# Apex_CV_Inputs_UI_v1_0.net
KiCad netlist of a schematic drawn in EAGLE
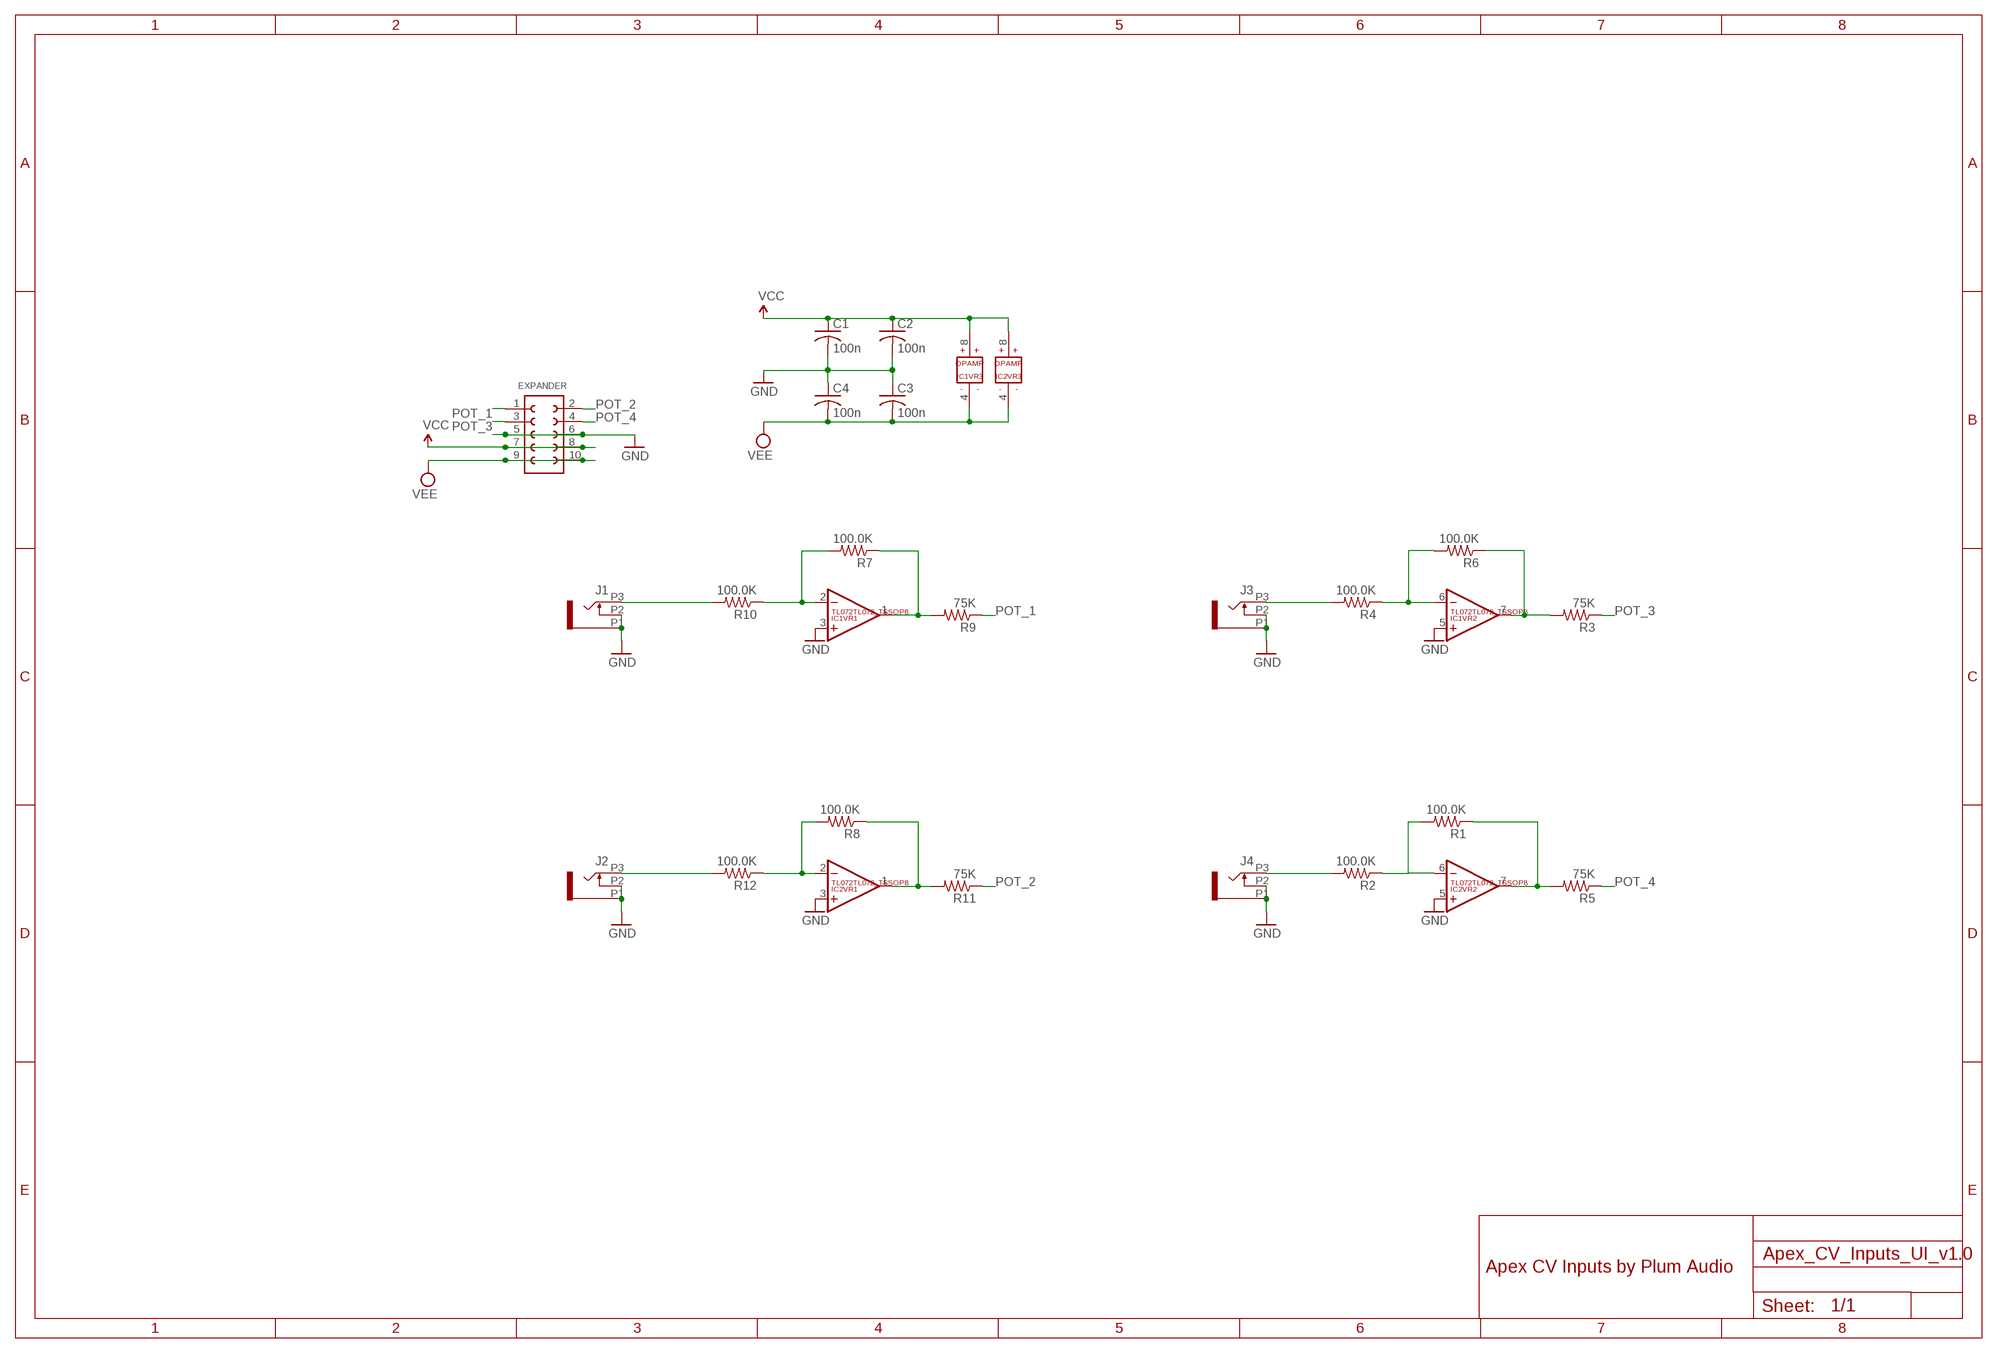
[diagram p0: schematic, sheet 1]

(export (version "E")
  (design (tool "Eeschema 10.0.6"))
  (components
    (comp (ref "C1")
      (value "100n")
      (footprint "eagle-import:C0603")
      (libsource (lib "eagle-import") (part "C-USC0603"))
    )
    (comp (ref "C2")
      (value "100n")
      (footprint "eagle-import:C0603")
      (libsource (lib "eagle-import") (part "C-USC0603"))
    )
    (comp (ref "C3")
      (value "100n")
      (footprint "eagle-import:C0603")
      (libsource (lib "eagle-import") (part "C-USC0603"))
    )
    (comp (ref "C4")
      (value "100n")
      (footprint "eagle-import:C0603")
      (libsource (lib "eagle-import") (part "C-USC0603"))
    )
    (comp (ref "EXPANDER")
      (value "61301021121")
      (footprint "eagle-import:61301021121")
      (libsource (lib "eagle-import") (part "61301021121"))
    )
    (comp (ref "IC1")
      (value "TL072TL072_TSSOP8")
      (footprint "eagle-import:TL072_TSSOP8")
      (libsource (lib "eagle-import") (part "TL072TL072_TSSOP8"))
    )
    (comp (ref "IC2")
      (value "TL072TL072_TSSOP8")
      (footprint "eagle-import:TL072_TSSOP8")
      (libsource (lib "eagle-import") (part "TL072TL072_TSSOP8"))
    )
    (comp (ref "J1")
      (value "OG-PJ301_PJ301_THONKICONN")
      (footprint "eagle-import:OG-PJ301_WQP_PJ_301M6_NO_HOLE")
      (libsource (lib "eagle-import") (part "OG-PJ301_PJ301_THONKICONN"))
    )
    (comp (ref "J2")
      (value "OG-PJ301_PJ301_THONKICONN")
      (footprint "eagle-import:OG-PJ301_WQP_PJ_301M6_NO_HOLE")
      (libsource (lib "eagle-import") (part "OG-PJ301_PJ301_THONKICONN"))
    )
    (comp (ref "J3")
      (value "OG-PJ301_PJ301_THONKICONN")
      (footprint "eagle-import:OG-PJ301_WQP_PJ_301M6_NO_HOLE")
      (libsource (lib "eagle-import") (part "OG-PJ301_PJ301_THONKICONN"))
    )
    (comp (ref "J4")
      (value "OG-PJ301_PJ301_THONKICONN")
      (footprint "eagle-import:OG-PJ301_WQP_PJ_301M6_NO_HOLE")
      (libsource (lib "eagle-import") (part "OG-PJ301_PJ301_THONKICONN"))
    )
    (comp (ref "R1")
      (value "100.0K")
      (footprint "eagle-import:R0603")
      (libsource (lib "eagle-import") (part "R-US_R0603"))
    )
    (comp (ref "R2")
      (value "100.0K")
      (footprint "eagle-import:R0603")
      (libsource (lib "eagle-import") (part "R-US_R0603"))
    )
    (comp (ref "R3")
      (value "75K")
      (footprint "eagle-import:R0603")
      (libsource (lib "eagle-import") (part "R-US_R0603"))
    )
    (comp (ref "R4")
      (value "100.0K")
      (footprint "eagle-import:R0603")
      (libsource (lib "eagle-import") (part "R-US_R0603"))
    )
    (comp (ref "R5")
      (value "75K")
      (footprint "eagle-import:R0603")
      (libsource (lib "eagle-import") (part "R-US_R0603"))
    )
    (comp (ref "R6")
      (value "100.0K")
      (footprint "eagle-import:R0603")
      (libsource (lib "eagle-import") (part "R-US_R0603"))
    )
    (comp (ref "R7")
      (value "100.0K")
      (footprint "eagle-import:R0603")
      (libsource (lib "eagle-import") (part "R-US_R0603"))
    )
    (comp (ref "R8")
      (value "100.0K")
      (footprint "eagle-import:R0603")
      (libsource (lib "eagle-import") (part "R-US_R0603"))
    )
    (comp (ref "R9")
      (value "75K")
      (footprint "eagle-import:R0603")
      (libsource (lib "eagle-import") (part "R-US_R0603"))
    )
    (comp (ref "R10")
      (value "100.0K")
      (footprint "eagle-import:R0603")
      (libsource (lib "eagle-import") (part "R-US_R0603"))
    )
    (comp (ref "R11")
      (value "75K")
      (footprint "eagle-import:R0603")
      (libsource (lib "eagle-import") (part "R-US_R0603"))
    )
    (comp (ref "R12")
      (value "100.0K")
      (footprint "eagle-import:R0603")
      (libsource (lib "eagle-import") (part "R-US_R0603"))
    )
  )
  (nets
    (net (code "1") (name "/POT_1") (class "Default")
      (node (ref "EXPANDER") (pin "1") (pinfunction "1_1") (pintype "passive"))
      (node (ref "R9") (pin "1") (pinfunction "1_1") (pintype "passive"))
    )
    (net (code "2") (name "/POT_2") (class "Default")
      (node (ref "EXPANDER") (pin "2") (pinfunction "10_2") (pintype "passive"))
      (node (ref "R11") (pin "1") (pinfunction "1_1") (pintype "passive"))
    )
    (net (code "3") (name "/POT_3") (class "Default")
      (node (ref "EXPANDER") (pin "3") (pinfunction "2_3") (pintype "passive"))
      (node (ref "R3") (pin "1") (pinfunction "1_1") (pintype "passive"))
    )
    (net (code "4") (name "/POT_4") (class "Default")
      (node (ref "EXPANDER") (pin "4") (pinfunction "9_4") (pintype "passive"))
      (node (ref "R5") (pin "1") (pinfunction "1_1") (pintype "passive"))
    )
    (net (code "5") (name "GND") (class "Default")
      (node (ref "C1") (pin "2") (pinfunction "2_2") (pintype "passive"))
      (node (ref "C2") (pin "2") (pinfunction "2_2") (pintype "passive"))
      (node (ref "C3") (pin "1") (pinfunction "1_1") (pintype "passive"))
      (node (ref "C4") (pin "1") (pinfunction "1_1") (pintype "passive"))
      (node (ref "EXPANDER") (pin "5") (pinfunction "3_5") (pintype "passive"))
      (node (ref "EXPANDER") (pin "6") (pinfunction "8_6") (pintype "passive"))
      (node (ref "IC1") (pin "3") (pinfunction "+IN_3") (pintype "input"))
      (node (ref "IC1") (pin "5") (pinfunction "+IN_5") (pintype "input"))
      (node (ref "IC2") (pin "3") (pinfunction "+IN_3") (pintype "input"))
      (node (ref "IC2") (pin "5") (pinfunction "+IN_5") (pintype "input"))
      (node (ref "J1") (pin "P1") (pinfunction "1_P1") (pintype "passive"))
      (node (ref "J1") (pin "P2") (pinfunction "2_P2") (pintype "passive"))
      (node (ref "J2") (pin "P1") (pinfunction "1_P1") (pintype "passive"))
      (node (ref "J2") (pin "P2") (pinfunction "2_P2") (pintype "passive"))
      (node (ref "J3") (pin "P1") (pinfunction "1_P1") (pintype "passive"))
      (node (ref "J3") (pin "P2") (pinfunction "2_P2") (pintype "passive"))
      (node (ref "J4") (pin "P1") (pinfunction "1_P1") (pintype "passive"))
      (node (ref "J4") (pin "P2") (pinfunction "2_P2") (pintype "passive"))
    )
    (net (code "6") (name "Net-(IC1A--IN)") (class "Default")
      (node (ref "IC1") (pin "2") (pinfunction "-IN_2") (pintype "input"))
      (node (ref "R10") (pin "1") (pinfunction "1_1") (pintype "passive"))
      (node (ref "R7") (pin "2") (pinfunction "2_2") (pintype "passive"))
    )
    (net (code "7") (name "Net-(IC1A-OUT)") (class "Default")
      (node (ref "IC1") (pin "1") (pinfunction "OUT_1") (pintype "output"))
      (node (ref "R7") (pin "1") (pinfunction "1_1") (pintype "passive"))
      (node (ref "R9") (pin "2") (pinfunction "2_2") (pintype "passive"))
    )
    (net (code "8") (name "Net-(IC1B--IN)") (class "Default")
      (node (ref "IC1") (pin "6") (pinfunction "-IN_6") (pintype "input"))
      (node (ref "R4") (pin "1") (pinfunction "1_1") (pintype "passive"))
      (node (ref "R6") (pin "2") (pinfunction "2_2") (pintype "passive"))
    )
    (net (code "9") (name "Net-(IC1B-OUT)") (class "Default")
      (node (ref "IC1") (pin "7") (pinfunction "OUT_7") (pintype "output"))
      (node (ref "R3") (pin "2") (pinfunction "2_2") (pintype "passive"))
      (node (ref "R6") (pin "1") (pinfunction "1_1") (pintype "passive"))
    )
    (net (code "10") (name "Net-(IC2A--IN)") (class "Default")
      (node (ref "IC2") (pin "2") (pinfunction "-IN_2") (pintype "input"))
      (node (ref "R12") (pin "1") (pinfunction "1_1") (pintype "passive"))
      (node (ref "R8") (pin "2") (pinfunction "2_2") (pintype "passive"))
    )
    (net (code "11") (name "Net-(IC2A-OUT)") (class "Default")
      (node (ref "IC2") (pin "1") (pinfunction "OUT_1") (pintype "output"))
      (node (ref "R11") (pin "2") (pinfunction "2_2") (pintype "passive"))
      (node (ref "R8") (pin "1") (pinfunction "1_1") (pintype "passive"))
    )
    (net (code "12") (name "Net-(IC2B--IN)") (class "Default")
      (node (ref "IC2") (pin "6") (pinfunction "-IN_6") (pintype "input"))
      (node (ref "R1") (pin "2") (pinfunction "2_2") (pintype "passive"))
      (node (ref "R2") (pin "1") (pinfunction "1_1") (pintype "passive"))
    )
    (net (code "13") (name "Net-(IC2B-OUT)") (class "Default")
      (node (ref "IC2") (pin "7") (pinfunction "OUT_7") (pintype "output"))
      (node (ref "R1") (pin "1") (pinfunction "1_1") (pintype "passive"))
      (node (ref "R5") (pin "2") (pinfunction "2_2") (pintype "passive"))
    )
    (net (code "14") (name "Net-(J1-3)") (class "Default")
      (node (ref "J1") (pin "P3") (pinfunction "3_P3") (pintype "passive"))
      (node (ref "R10") (pin "2") (pinfunction "2_2") (pintype "passive"))
    )
    (net (code "15") (name "Net-(J2-3)") (class "Default")
      (node (ref "J2") (pin "P3") (pinfunction "3_P3") (pintype "passive"))
      (node (ref "R12") (pin "2") (pinfunction "2_2") (pintype "passive"))
    )
    (net (code "16") (name "Net-(J3-3)") (class "Default")
      (node (ref "J3") (pin "P3") (pinfunction "3_P3") (pintype "passive"))
      (node (ref "R4") (pin "2") (pinfunction "2_2") (pintype "passive"))
    )
    (net (code "17") (name "Net-(J4-3)") (class "Default")
      (node (ref "J4") (pin "P3") (pinfunction "3_P3") (pintype "passive"))
      (node (ref "R2") (pin "2") (pinfunction "2_2") (pintype "passive"))
    )
    (net (code "18") (name "VCC") (class "Default")
      (node (ref "C1") (pin "1") (pinfunction "1_1") (pintype "passive"))
      (node (ref "C2") (pin "1") (pinfunction "1_1") (pintype "passive"))
      (node (ref "EXPANDER") (pin "7") (pinfunction "4_7") (pintype "passive"))
      (node (ref "EXPANDER") (pin "8") (pinfunction "7_8") (pintype "passive"))
      (node (ref "IC1") (pin "8") (pinfunction "V+_8") (pintype "power_in"))
      (node (ref "IC2") (pin "8") (pinfunction "V+_8") (pintype "power_in"))
    )
    (net (code "19") (name "VEE") (class "Default")
      (node (ref "C3") (pin "2") (pinfunction "2_2") (pintype "passive"))
      (node (ref "C4") (pin "2") (pinfunction "2_2") (pintype "passive"))
      (node (ref "EXPANDER") (pin "10") (pinfunction "6_10") (pintype "passive"))
      (node (ref "EXPANDER") (pin "9") (pinfunction "5_9") (pintype "passive"))
      (node (ref "IC1") (pin "4") (pinfunction "V-_4") (pintype "power_in"))
      (node (ref "IC2") (pin "4") (pinfunction "V-_4") (pintype "power_in"))
    )
  )
)
